# ACCEL_SENSOR.net
KiCad netlist of a schematic drawn in EAGLE
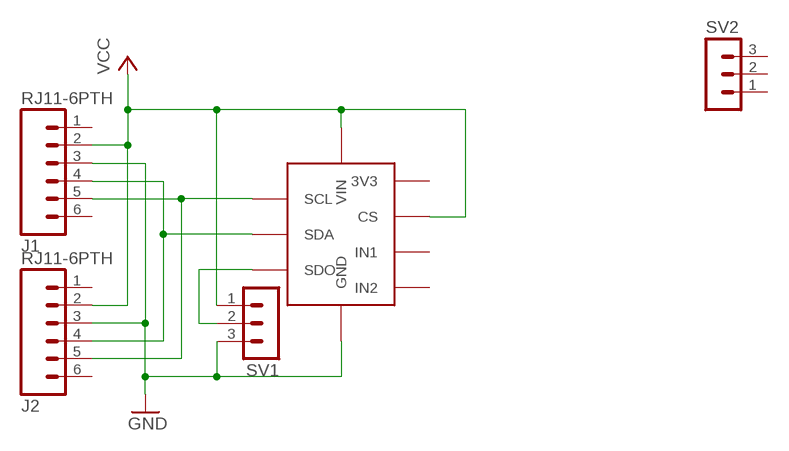
[diagram p0: schematic, sheet 1]

(export (version "E")
  (design (tool "Eeschema 10.0.6"))
  (components
    (comp (ref "J1")
      (value "RJ11-6PTH")
      (footprint "eagle-import:RJ11-6")
      (libsource (lib "eagle-import") (part "RJ11-6PTH"))
    )
    (comp (ref "J2")
      (value "RJ11-6PTH")
      (footprint "eagle-import:RJ11-6")
      (libsource (lib "eagle-import") (part "RJ11-6PTH"))
    )
    (comp (ref "SV1")
      (value "MA03-1")
      (footprint "eagle-import:MA03-1")
      (libsource (lib "eagle-import") (part "MA03-1"))
    )
    (comp (ref "SV2")
      (value "MA03-1")
      (footprint "eagle-import:MA03-1")
      (libsource (lib "eagle-import") (part "MA03-1"))
    )
    (comp (ref "U$1")
      (value "ADXL345")
      (footprint "eagle-import:ADXL345")
      (libsource (lib "eagle-import") (part "ADXL345"))
    )
  )
  (nets
    (net (code "1") (name "GND") (class "Default")
      (node (ref "J1") (pin "3") (pinfunction "3_3") (pintype "passive"))
      (node (ref "J2") (pin "3") (pinfunction "3_3") (pintype "passive"))
      (node (ref "SV1") (pin "3") (pinfunction "3_3") (pintype "passive"))
      (node (ref "U$1") (pin "GND") (pinfunction "GND_GND") (pintype "bidirectional"))
    )
    (net (code "2") (name "Net-(J1-Pad4)") (class "Default")
      (node (ref "J1") (pin "4") (pinfunction "4_4") (pintype "passive"))
      (node (ref "J2") (pin "4") (pinfunction "4_4") (pintype "passive"))
      (node (ref "U$1") (pin "SDA") (pinfunction "SDA_SDA") (pintype "bidirectional"))
    )
    (net (code "3") (name "Net-(J1-Pad5)") (class "Default")
      (node (ref "J1") (pin "5") (pinfunction "5_5") (pintype "passive"))
      (node (ref "J2") (pin "5") (pinfunction "5_5") (pintype "passive"))
      (node (ref "U$1") (pin "SCL") (pinfunction "SCL_SCL") (pintype "bidirectional"))
    )
    (net (code "4") (name "Net-(SV1-Pad2)") (class "Default")
      (node (ref "SV1") (pin "2") (pinfunction "2_2") (pintype "passive"))
      (node (ref "U$1") (pin "SDO") (pinfunction "SDO_SDO") (pintype "bidirectional"))
    )
    (net (code "5") (name "VCC") (class "Default")
      (node (ref "J1") (pin "2") (pinfunction "2_2") (pintype "passive"))
      (node (ref "J2") (pin "2") (pinfunction "2_2") (pintype "passive"))
      (node (ref "SV1") (pin "1") (pinfunction "1_1") (pintype "passive"))
      (node (ref "U$1") (pin "CS") (pinfunction "CS_CS") (pintype "bidirectional"))
      (node (ref "U$1") (pin "VIN") (pinfunction "VIN_VIN") (pintype "bidirectional"))
    )
    (net (code "6") (name "unconnected-(J1-Pad1)") (class "Default")
      (node (ref "J1") (pin "1") (pinfunction "1_1") (pintype "passive"))
    )
    (net (code "7") (name "unconnected-(J1-Pad6)") (class "Default")
      (node (ref "J1") (pin "6") (pinfunction "6_6") (pintype "passive"))
    )
    (net (code "8") (name "unconnected-(J2-Pad1)") (class "Default")
      (node (ref "J2") (pin "1") (pinfunction "1_1") (pintype "passive"))
    )
    (net (code "9") (name "unconnected-(J2-Pad6)") (class "Default")
      (node (ref "J2") (pin "6") (pinfunction "6_6") (pintype "passive"))
    )
    (net (code "10") (name "unconnected-(SV2-Pad1)") (class "Default")
      (node (ref "SV2") (pin "1") (pinfunction "1_1") (pintype "passive"))
    )
    (net (code "11") (name "unconnected-(SV2-Pad2)") (class "Default")
      (node (ref "SV2") (pin "2") (pinfunction "2_2") (pintype "passive"))
    )
    (net (code "12") (name "unconnected-(SV2-Pad3)") (class "Default")
      (node (ref "SV2") (pin "3") (pinfunction "3_3") (pintype "passive"))
    )
    (net (code "13") (name "unconnected-(U$1-IN1-PadINT1)") (class "Default")
      (node (ref "U$1") (pin "INT1") (pinfunction "IN1_INT1") (pintype "bidirectional"))
    )
    (net (code "14") (name "unconnected-(U$1-IN2-PadINT2)") (class "Default")
      (node (ref "U$1") (pin "INT2") (pinfunction "IN2_INT2") (pintype "bidirectional"))
    )
    (net (code "15") (name "unconnected-(U$1-Pad3V3)") (class "Default")
      (node (ref "U$1") (pin "3V3") (pinfunction "3V3_3V3") (pintype "bidirectional"))
    )
  )
)
